# Pratica_00.net
KiCad netlist of a schematic drawn in EasyEDA
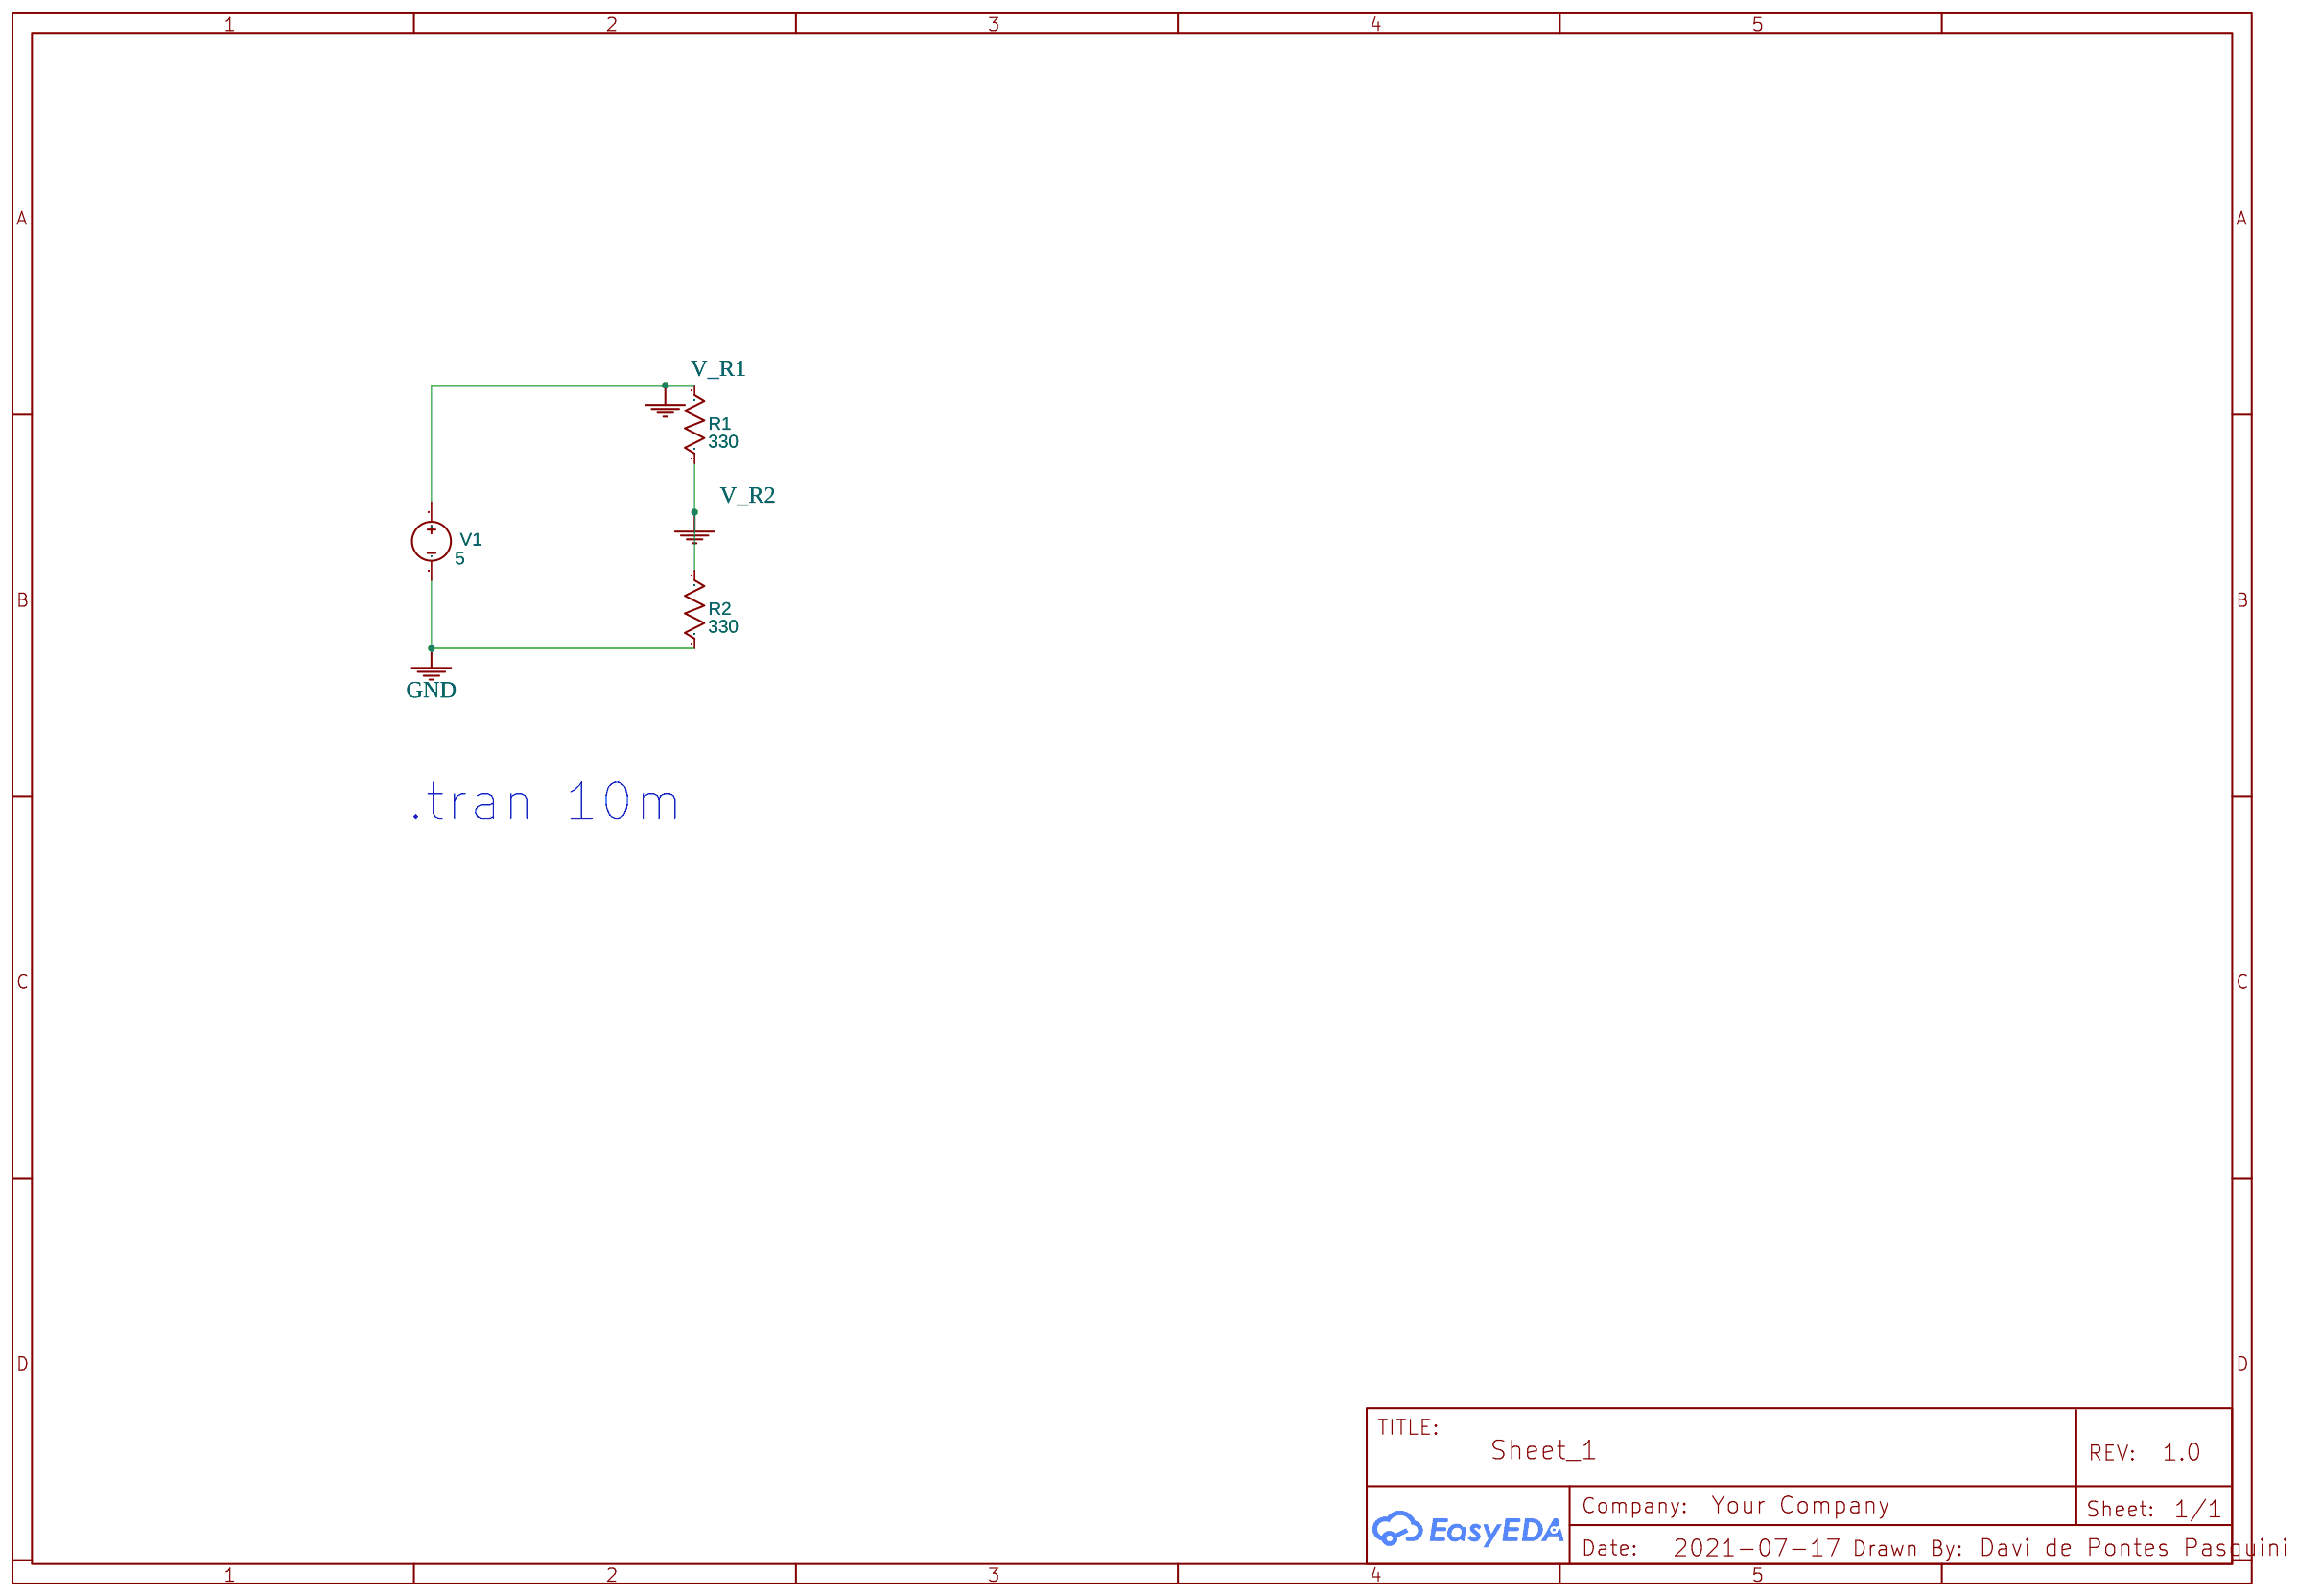
[diagram p0: schematic sheet]

(export (version "E")
  (design (tool "Eeschema 10.0.6"))
  (components
    (comp (ref "R1") (value "330") (libsource (lib "") (part "Resistor_US")))
    (comp (ref "R2") (value "330") (libsource (lib "") (part "Resistor_US")))
    (comp (ref "V1") (value "5") (libsource (lib "") (part "VDC")))
  )
  (nets
    (net (code "1") (name "GND") (class "Default")
      (node (ref "R2") (pin "1") (pinfunction "1_1") (pintype "unspecified"))
      (node (ref "V1") (pin "2") (pinfunction "2_2") (pintype "unspecified"))
    )
    (net (code "2") (name "V_R1") (class "Default")
      (node (ref "R1") (pin "2") (pinfunction "2_2") (pintype "unspecified"))
      (node (ref "V1") (pin "1") (pinfunction "1_1") (pintype "unspecified"))
    )
    (net (code "3") (name "V_R2") (class "Default")
      (node (ref "R1") (pin "1") (pinfunction "1_1") (pintype "unspecified"))
      (node (ref "R2") (pin "2") (pinfunction "2_2") (pintype "unspecified"))
    )
  )
)
